# Power_Dist.net
KiCad netlist of a schematic drawn in EAGLE
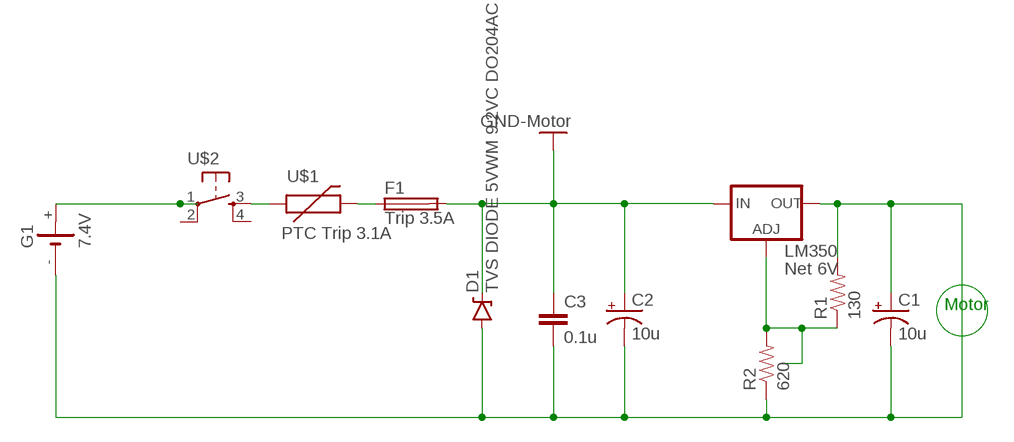
[diagram p0: schematic, sheet 1]

(export (version "E")
  (design (tool "Eeschema 10.0.6"))
  (components
    (comp (ref "C1")
      (value "10u")
      (footprint "eagle-import:CPOL-RADIAL-10UF-25V")
      (libsource (lib "eagle-import") (part "CAP_POLPTH2"))
    )
    (comp (ref "C2")
      (value "10u")
      (footprint "eagle-import:CPOL-RADIAL-10UF-25V")
      (libsource (lib "eagle-import") (part "CAP_POLPTH2"))
    )
    (comp (ref "C3")
      (value "0.1u")
      (footprint "eagle-import:CAP-PTH-SMALL-KIT")
      (libsource (lib "eagle-import") (part "0.1UF-50V-20%(PTH)KIT-EZ"))
    )
    (comp (ref "D1")
      (value "TVS DIODE 5VWM 9.2VC DO204AC")
      (footprint "eagle-import:DIODE-BZT52")
      (libsource (lib "eagle-import") (part "DIODE-ZENER"))
    )
    (comp (ref "F1")
      (value "Trip 3.5A")
      (footprint "eagle-import:19559")
      (fields (field (name "MPN") "55900000001"))
      (libsource (lib "eagle-import") (part "19559"))
    )
    (comp (ref "G1")
      (value "7.4V")
      (footprint "eagle-import:SL-340_P3.6V")
      (libsource (lib "eagle-import") (part "SL-340/P3.6V"))
    )
    (comp (ref "LM350")
      (value "Net 6V")
      (footprint "eagle-import:V-REG_DPACK")
      (libsource (lib "eagle-import") (part "V_REG_317DPACK"))
    )
    (comp (ref "R1")
      (value "130")
      (footprint "eagle-import:AXIAL-0.5")
      (libsource (lib "eagle-import") (part "RESISTORPTH-1/2W"))
    )
    (comp (ref "R2")
      (value "620")
      (footprint "eagle-import:AXIAL-0.5")
      (libsource (lib "eagle-import") (part "RESISTORPTH-1/2W"))
    )
    (comp (ref "U$1")
      (value "PTC Trip 3.1A")
      (footprint "eagle-import:MC331XX")
      (libsource (lib "eagle-import") (part "PTC"))
    )
    (comp (ref "U$2")
      (value "TACTILE-SWITCH-7914G")
      (footprint "eagle-import:7914G")
      (libsource (lib "eagle-import") (part "TACTILE-SWITCH-7914G"))
    )
  )
  (nets
    (net (code "1") (name "GND-Motor") (class "Default")
      (node (ref "C2") (pin "1") (pinfunction "+_1") (pintype "passive"))
      (node (ref "C3") (pin "1") (pinfunction "1_1") (pintype "passive"))
      (node (ref "D1") (pin "C") (pinfunction "C_C") (pintype "passive"))
      (node (ref "F1") (pin "2") (pinfunction "2_2") (pintype "passive"))
      (node (ref "LM350") (pin "3") (pinfunction "IN_3") (pintype "input"))
    )
    (net (code "2") (name "Net-(C1-+)") (class "Default")
      (node (ref "C1") (pin "1") (pinfunction "+_1") (pintype "passive"))
      (node (ref "C1") (pin "2") (pinfunction "-_2") (pintype "passive"))
      (node (ref "C2") (pin "2") (pinfunction "-_2") (pintype "passive"))
      (node (ref "C3") (pin "2") (pinfunction "2_2") (pintype "passive"))
      (node (ref "D1") (pin "A") (pinfunction "A_A") (pintype "passive"))
      (node (ref "G1") (pin "-") (pinfunction "-_-") (pintype "passive"))
      (node (ref "LM350") (pin "4") (pinfunction "OUT_4") (pintype "output"))
      (node (ref "R1") (pin "P$2") (pinfunction "2_P$2") (pintype "passive"))
      (node (ref "R2") (pin "P$1") (pinfunction "1_P$1") (pintype "passive"))
    )
    (net (code "3") (name "Net-(G1-Pad+)") (class "Default")
      (node (ref "G1") (pin "+") (pinfunction "+_+") (pintype "passive"))
      (node (ref "U$2") (pin "1") (pinfunction "1_1") (pintype "passive"))
    )
    (net (code "4") (name "Net-(LM350-ADJ)") (class "Default")
      (node (ref "LM350") (pin "1") (pinfunction "ADJ_1") (pintype "input"))
      (node (ref "R1") (pin "P$1") (pinfunction "1_P$1") (pintype "passive"))
      (node (ref "R2") (pin "P$2") (pinfunction "2_P$2") (pintype "passive"))
    )
    (net (code "5") (name "Net-(U$1-1)") (class "Default")
      (node (ref "U$1") (pin "P$1") (pinfunction "1_P$1") (pintype "bidirectional"))
      (node (ref "U$2") (pin "3") (pinfunction "3_3") (pintype "passive"))
    )
    (net (code "6") (name "Net-(U$1-2)") (class "Default")
      (node (ref "F1") (pin "1") (pinfunction "1_1") (pintype "passive"))
      (node (ref "U$1") (pin "P$2") (pinfunction "2_P$2") (pintype "bidirectional"))
    )
    (net (code "7") (name "unconnected-(U$2-Pad2)") (class "Default")
      (node (ref "U$2") (pin "2") (pinfunction "2_2") (pintype "passive"))
    )
    (net (code "8") (name "unconnected-(U$2-Pad4)") (class "Default")
      (node (ref "U$2") (pin "4") (pinfunction "4_4") (pintype "passive"))
    )
  )
)
